# top_schem.net
KiCad netlist of a schematic drawn in Altium Designer
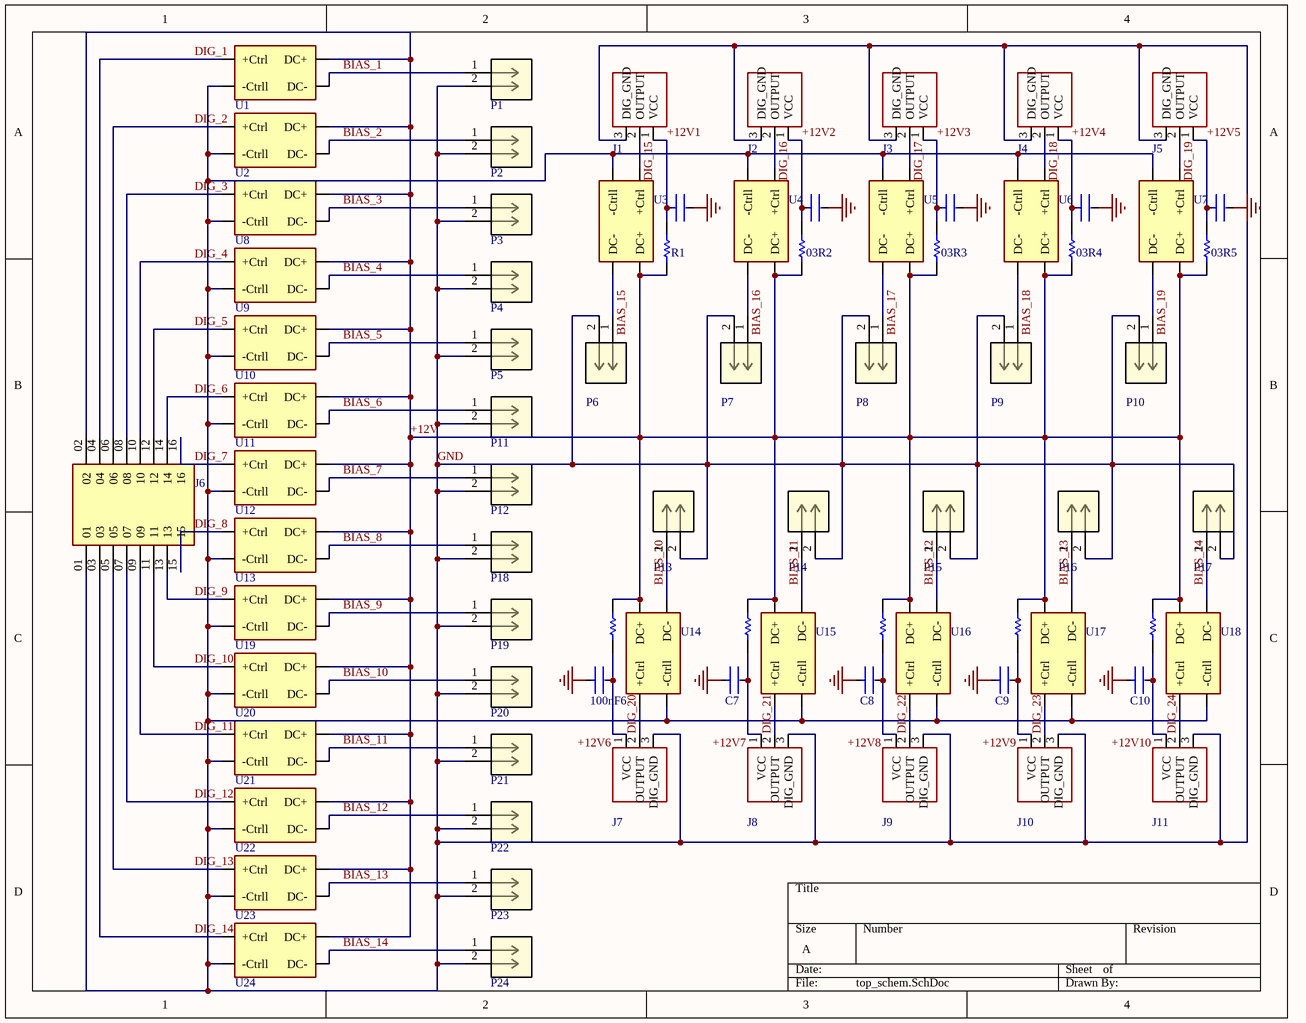
[diagram p0: top_schem.SchDoc]

(export (version "E")
  (design (tool "Eeschema 10.0.6"))
  (components
    (comp (ref "03R2")
      (value "ERJ-2BQJR30X")
      (footprint "03 Ohm")
      (description "RES 0.3 OHM 5% 1/6W 0402")
      (fields (field (name "MANUFACTURER") "Panasonic") (field (name "TOLERANCE") "5%"))
      (libsource (lib "ps_schlib") (part "ERJ-2BQJR30X"))
    )
    (comp (ref "03R3")
      (value "ERJ-2BQJR30X")
      (footprint "03 Ohm")
      (description "RES 0.3 OHM 5% 1/6W 0402")
      (fields (field (name "MANUFACTURER") "Panasonic") (field (name "TOLERANCE") "5%"))
      (libsource (lib "ps_schlib") (part "ERJ-2BQJR30X"))
    )
    (comp (ref "03R4")
      (value "ERJ-2BQJR30X")
      (footprint "03 Ohm")
      (description "RES 0.3 OHM 5% 1/6W 0402")
      (fields (field (name "MANUFACTURER") "Panasonic") (field (name "TOLERANCE") "5%"))
      (libsource (lib "ps_schlib") (part "ERJ-2BQJR30X"))
    )
    (comp (ref "03R5")
      (value "ERJ-2BQJR30X")
      (footprint "03 Ohm")
      (description "RES 0.3 OHM 5% 1/6W 0402")
      (fields (field (name "MANUFACTURER") "Panasonic") (field (name "TOLERANCE") "5%"))
      (libsource (lib "ps_schlib") (part "ERJ-2BQJR30X"))
    )
    (comp (ref "03R7")
      (value "ERJ-2BQJR30X")
      (footprint "03 Ohm")
      (description "RES 0.3 OHM 5% 1/6W 0402")
      (fields (field (name "MANUFACTURER") "Panasonic") (field (name "TOLERANCE") "5%"))
      (libsource (lib "ps_schlib") (part "ERJ-2BQJR30X"))
    )
    (comp (ref "03R8")
      (value "ERJ-2BQJR30X")
      (footprint "03 Ohm")
      (description "RES 0.3 OHM 5% 1/6W 0402")
      (fields (field (name "MANUFACTURER") "Panasonic") (field (name "TOLERANCE") "5%"))
      (libsource (lib "ps_schlib") (part "ERJ-2BQJR30X"))
    )
    (comp (ref "03R9")
      (value "ERJ-2BQJR30X")
      (footprint "03 Ohm")
      (description "RES 0.3 OHM 5% 1/6W 0402")
      (fields (field (name "MANUFACTURER") "Panasonic") (field (name "TOLERANCE") "5%"))
      (libsource (lib "ps_schlib") (part "ERJ-2BQJR30X"))
    )
    (comp (ref "03R10")
      (value "ERJ-2BQJR30X")
      (footprint "03 Ohm")
      (description "RES 0.3 OHM 5% 1/6W 0402")
      (fields (field (name "MANUFACTURER") "Panasonic") (field (name "TOLERANCE") "5%"))
      (libsource (lib "ps_schlib") (part "ERJ-2BQJR30X"))
    )
    (comp (ref "100nF1")
      (value "C0805C104K5RACTU")
      (footprint "100nF")
      (description "Cap Ceramic 0.1uF 50V X7R 10% SMD 2.0 x 1.2 mm 125 C Paper T/R")
      (fields (field (name "MANUFACTURER") "KEMET") (field (name "TOLERANCE") "10%"))
      (libsource (lib "ps_schlib") (part "C0805C104K5RACTU"))
    )
    (comp (ref "100nF6")
      (value "C0805C104K5RACTU")
      (footprint "100nF")
      (description "Cap Ceramic 0.1uF 50V X7R 10% SMD 2.0 x 1.2 mm 125 C Paper T/R")
      (fields (field (name "MANUFACTURER") "KEMET") (field (name "TOLERANCE") "10%"))
      (libsource (lib "ps_schlib") (part "C0805C104K5RACTU"))
    )
    (comp (ref "C2")
      (value "C0805C104K5RACTU")
      (footprint "100nF")
      (description "Cap Ceramic 0.1uF 50V X7R 10% SMD 2.0 x 1.2 mm 125 C Paper T/R")
      (fields (field (name "MANUFACTURER") "KEMET") (field (name "TOLERANCE") "10%"))
      (libsource (lib "ps_schlib") (part "C0805C104K5RACTU"))
    )
    (comp (ref "C3")
      (value "C0805C104K5RACTU")
      (footprint "100nF")
      (description "Cap Ceramic 0.1uF 50V X7R 10% SMD 2.0 x 1.2 mm 125 C Paper T/R")
      (fields (field (name "MANUFACTURER") "KEMET") (field (name "TOLERANCE") "10%"))
      (libsource (lib "ps_schlib") (part "C0805C104K5RACTU"))
    )
    (comp (ref "C4")
      (value "C0805C104K5RACTU")
      (footprint "100nF")
      (description "Cap Ceramic 0.1uF 50V X7R 10% SMD 2.0 x 1.2 mm 125 C Paper T/R")
      (fields (field (name "MANUFACTURER") "KEMET") (field (name "TOLERANCE") "10%"))
      (libsource (lib "ps_schlib") (part "C0805C104K5RACTU"))
    )
    (comp (ref "C5")
      (value "C0805C104K5RACTU")
      (footprint "100nF")
      (description "Cap Ceramic 0.1uF 50V X7R 10% SMD 2.0 x 1.2 mm 125 C Paper T/R")
      (fields (field (name "MANUFACTURER") "KEMET") (field (name "TOLERANCE") "10%"))
      (libsource (lib "ps_schlib") (part "C0805C104K5RACTU"))
    )
    (comp (ref "C7")
      (value "C0805C104K5RACTU")
      (footprint "100nF")
      (description "Cap Ceramic 0.1uF 50V X7R 10% SMD 2.0 x 1.2 mm 125 C Paper T/R")
      (fields (field (name "MANUFACTURER") "KEMET") (field (name "TOLERANCE") "10%"))
      (libsource (lib "ps_schlib") (part "C0805C104K5RACTU"))
    )
    (comp (ref "C8")
      (value "C0805C104K5RACTU")
      (footprint "100nF")
      (description "Cap Ceramic 0.1uF 50V X7R 10% SMD 2.0 x 1.2 mm 125 C Paper T/R")
      (fields (field (name "MANUFACTURER") "KEMET") (field (name "TOLERANCE") "10%"))
      (libsource (lib "ps_schlib") (part "C0805C104K5RACTU"))
    )
    (comp (ref "C9")
      (value "C0805C104K5RACTU")
      (footprint "100nF")
      (description "Cap Ceramic 0.1uF 50V X7R 10% SMD 2.0 x 1.2 mm 125 C Paper T/R")
      (fields (field (name "MANUFACTURER") "KEMET") (field (name "TOLERANCE") "10%"))
      (libsource (lib "ps_schlib") (part "C0805C104K5RACTU"))
    )
    (comp (ref "C10")
      (value "C0805C104K5RACTU")
      (footprint "100nF")
      (description "Cap Ceramic 0.1uF 50V X7R 10% SMD 2.0 x 1.2 mm 125 C Paper T/R")
      (fields (field (name "MANUFACTURER") "KEMET") (field (name "TOLERANCE") "10%"))
      (libsource (lib "ps_schlib") (part "C0805C104K5RACTU"))
    )
    (comp (ref "J1")
      (value "IF-D95T")
      (footprint "IF-D95")
      (description "DETECTOR PHOTOLOGIC TTL/CMOS")
      (fields (field (name "MANUFACTURER") "Industrial Fiber Optics"))
      (libsource (lib "ps_schlib") (part "IF-D95T"))
    )
    (comp (ref "J2")
      (value "IF-D95T")
      (footprint "IF-D95")
      (description "DETECTOR PHOTOLOGIC TTL/CMOS")
      (fields (field (name "MANUFACTURER") "Industrial Fiber Optics"))
      (libsource (lib "ps_schlib") (part "IF-D95T"))
    )
    (comp (ref "J3")
      (value "IF-D95T")
      (footprint "IF-D95")
      (description "DETECTOR PHOTOLOGIC TTL/CMOS")
      (fields (field (name "MANUFACTURER") "Industrial Fiber Optics"))
      (libsource (lib "ps_schlib") (part "IF-D95T"))
    )
    (comp (ref "J4")
      (value "IF-D95T")
      (footprint "IF-D95")
      (description "DETECTOR PHOTOLOGIC TTL/CMOS")
      (fields (field (name "MANUFACTURER") "Industrial Fiber Optics"))
      (libsource (lib "ps_schlib") (part "IF-D95T"))
    )
    (comp (ref "J5")
      (value "IF-D95T")
      (footprint "IF-D95")
      (description "DETECTOR PHOTOLOGIC TTL/CMOS")
      (fields (field (name "MANUFACTURER") "Industrial Fiber Optics"))
      (libsource (lib "ps_schlib") (part "IF-D95T"))
    )
    (comp (ref "J6")
      (value "SSM-108-X-DV")
      (footprint "16 pin header")
      (libsource (lib "ps_schlib") (part "SSM-108-X-DV"))
    )
    (comp (ref "J7")
      (value "IF-D95T")
      (footprint "IF-D95")
      (description "DETECTOR PHOTOLOGIC TTL/CMOS")
      (fields (field (name "MANUFACTURER") "Industrial Fiber Optics"))
      (libsource (lib "ps_schlib") (part "IF-D95T"))
    )
    (comp (ref "J8")
      (value "IF-D95T")
      (footprint "IF-D95")
      (description "DETECTOR PHOTOLOGIC TTL/CMOS")
      (fields (field (name "MANUFACTURER") "Industrial Fiber Optics"))
      (libsource (lib "ps_schlib") (part "IF-D95T"))
    )
    (comp (ref "J9")
      (value "IF-D95T")
      (footprint "IF-D95")
      (description "DETECTOR PHOTOLOGIC TTL/CMOS")
      (fields (field (name "MANUFACTURER") "Industrial Fiber Optics"))
      (libsource (lib "ps_schlib") (part "IF-D95T"))
    )
    (comp (ref "J10")
      (value "IF-D95T")
      (footprint "IF-D95")
      (description "DETECTOR PHOTOLOGIC TTL/CMOS")
      (fields (field (name "MANUFACTURER") "Industrial Fiber Optics"))
      (libsource (lib "ps_schlib") (part "IF-D95T"))
    )
    (comp (ref "J11")
      (value "IF-D95T")
      (footprint "IF-D95")
      (description "DETECTOR PHOTOLOGIC TTL/CMOS")
      (fields (field (name "MANUFACTURER") "Industrial Fiber Optics"))
      (libsource (lib "ps_schlib") (part "IF-D95T"))
    )
    (comp (ref "P1")
      (value "1054311102")
      (footprint "CONN_1054311102_MOL")
      (fields (field (name "MANUFACTURER") "Molex"))
      (libsource (lib "ps_schlib") (part "1054311102"))
    )
    (comp (ref "P2")
      (value "1054311102")
      (footprint "CONN_1054311102_MOL")
      (fields (field (name "MANUFACTURER") "Molex"))
      (libsource (lib "ps_schlib") (part "1054311102"))
    )
    (comp (ref "P3")
      (value "1054311102")
      (footprint "CONN_1054311102_MOL")
      (fields (field (name "MANUFACTURER") "Molex"))
      (libsource (lib "ps_schlib") (part "1054311102"))
    )
    (comp (ref "P4")
      (value "1054311102")
      (footprint "CONN_1054311102_MOL")
      (fields (field (name "MANUFACTURER") "Molex"))
      (libsource (lib "ps_schlib") (part "1054311102"))
    )
    (comp (ref "P5")
      (value "1054311102")
      (footprint "CONN_1054311102_MOL")
      (fields (field (name "MANUFACTURER") "Molex"))
      (libsource (lib "ps_schlib") (part "1054311102"))
    )
    (comp (ref "P6")
      (value "1054311102")
      (footprint "CONN_1054311102_MOL")
      (fields (field (name "MANUFACTURER") "Molex"))
      (libsource (lib "") (part "1054311102_1"))
    )
    (comp (ref "P7")
      (value "1054311102")
      (footprint "CONN_1054311102_MOL")
      (fields (field (name "MANUFACTURER") "Molex"))
      (libsource (lib "") (part "1054311102_1"))
    )
    (comp (ref "P8")
      (value "1054311102")
      (footprint "CONN_1054311102_MOL")
      (fields (field (name "MANUFACTURER") "Molex"))
      (libsource (lib "") (part "1054311102_1"))
    )
    (comp (ref "P9")
      (value "1054311102")
      (footprint "CONN_1054311102_MOL")
      (fields (field (name "MANUFACTURER") "Molex"))
      (libsource (lib "") (part "1054311102_1"))
    )
    (comp (ref "P10")
      (value "1054311102")
      (footprint "CONN_1054311102_MOL")
      (fields (field (name "MANUFACTURER") "Molex"))
      (libsource (lib "") (part "1054311102_1"))
    )
    (comp (ref "P11")
      (value "1054311102")
      (footprint "CONN_1054311102_MOL")
      (fields (field (name "MANUFACTURER") "Molex"))
      (libsource (lib "ps_schlib") (part "1054311102"))
    )
    (comp (ref "P12")
      (value "1054311102")
      (footprint "CONN_1054311102_MOL")
      (fields (field (name "MANUFACTURER") "Molex"))
      (libsource (lib "ps_schlib") (part "1054311102"))
    )
    (comp (ref "P13")
      (value "1054311102")
      (footprint "CONN_1054311102_MOL")
      (fields (field (name "MANUFACTURER") "Molex"))
      (libsource (lib "") (part "1054311102_2"))
    )
    (comp (ref "P14")
      (value "1054311102")
      (footprint "CONN_1054311102_MOL")
      (fields (field (name "MANUFACTURER") "Molex"))
      (libsource (lib "") (part "1054311102_2"))
    )
    (comp (ref "P15")
      (value "1054311102")
      (footprint "CONN_1054311102_MOL")
      (fields (field (name "MANUFACTURER") "Molex"))
      (libsource (lib "") (part "1054311102_2"))
    )
    (comp (ref "P16")
      (value "1054311102")
      (footprint "CONN_1054311102_MOL")
      (fields (field (name "MANUFACTURER") "Molex"))
      (libsource (lib "") (part "1054311102_2"))
    )
    (comp (ref "P17")
      (value "1054311102")
      (footprint "CONN_1054311102_MOL")
      (fields (field (name "MANUFACTURER") "Molex"))
      (libsource (lib "") (part "1054311102_2"))
    )
    (comp (ref "P18")
      (value "1054311102")
      (footprint "CONN_1054311102_MOL")
      (fields (field (name "MANUFACTURER") "Molex"))
      (libsource (lib "ps_schlib") (part "1054311102"))
    )
    (comp (ref "P19")
      (value "1054311102")
      (footprint "CONN_1054311102_MOL")
      (fields (field (name "MANUFACTURER") "Molex"))
      (libsource (lib "ps_schlib") (part "1054311102"))
    )
    (comp (ref "P20")
      (value "1054311102")
      (footprint "CONN_1054311102_MOL")
      (fields (field (name "MANUFACTURER") "Molex"))
      (libsource (lib "ps_schlib") (part "1054311102"))
    )
    (comp (ref "P21")
      (value "1054311102")
      (footprint "CONN_1054311102_MOL")
      (fields (field (name "MANUFACTURER") "Molex"))
      (libsource (lib "ps_schlib") (part "1054311102"))
    )
    (comp (ref "P22")
      (value "1054311102")
      (footprint "CONN_1054311102_MOL")
      (fields (field (name "MANUFACTURER") "Molex"))
      (libsource (lib "ps_schlib") (part "1054311102"))
    )
    (comp (ref "P23")
      (value "1054311102")
      (footprint "CONN_1054311102_MOL")
      (fields (field (name "MANUFACTURER") "Molex"))
      (libsource (lib "ps_schlib") (part "1054311102"))
    )
    (comp (ref "P24")
      (value "1054311102")
      (footprint "CONN_1054311102_MOL")
      (fields (field (name "MANUFACTURER") "Molex"))
      (libsource (lib "ps_schlib") (part "1054311102"))
    )
    (comp (ref "R1")
      (value "ERJ-2BQJR30X")
      (footprint "03 Ohm")
      (description "RES 0.3 OHM 5% 1/6W 0402")
      (fields (field (name "MANUFACTURER") "Panasonic") (field (name "TOLERANCE") "5%"))
      (libsource (lib "ps_schlib") (part "ERJ-2BQJR30X"))
    )
    (comp (ref "R6")
      (value "ERJ-2BQJR30X")
      (footprint "03 Ohm")
      (description "RES 0.3 OHM 5% 1/6W 0402")
      (fields (field (name "MANUFACTURER") "Panasonic") (field (name "TOLERANCE") "5%"))
      (libsource (lib "ps_schlib") (part "ERJ-2BQJR30X"))
    )
    (comp (ref "U1")
      (value "Solid state relay")
      (footprint "CPC1002N")
      (libsource (lib "ps_schlib") (part "CPC1002N"))
    )
    (comp (ref "U2")
      (value "Solid state relay")
      (footprint "CPC1002N")
      (libsource (lib "ps_schlib") (part "CPC1002N"))
    )
    (comp (ref "U3")
      (value "Solid state relay")
      (footprint "CPC1002N")
      (libsource (lib "") (part "CPC1002N_2"))
    )
    (comp (ref "U4")
      (value "Solid state relay")
      (footprint "CPC1002N")
      (libsource (lib "") (part "CPC1002N_2"))
    )
    (comp (ref "U5")
      (value "Solid state relay")
      (footprint "CPC1002N")
      (libsource (lib "") (part "CPC1002N_2"))
    )
    (comp (ref "U6")
      (value "Solid state relay")
      (footprint "CPC1002N")
      (libsource (lib "") (part "CPC1002N_2"))
    )
    (comp (ref "U7")
      (value "Solid state relay")
      (footprint "CPC1002N")
      (libsource (lib "") (part "CPC1002N_2"))
    )
    (comp (ref "U8")
      (value "Solid state relay")
      (footprint "CPC1002N")
      (libsource (lib "ps_schlib") (part "CPC1002N"))
    )
    (comp (ref "U9")
      (value "Solid state relay")
      (footprint "CPC1002N")
      (libsource (lib "ps_schlib") (part "CPC1002N"))
    )
    (comp (ref "U10")
      (value "Solid state relay")
      (footprint "CPC1002N")
      (libsource (lib "ps_schlib") (part "CPC1002N"))
    )
    (comp (ref "U11")
      (value "Solid state relay")
      (footprint "CPC1002N")
      (libsource (lib "ps_schlib") (part "CPC1002N"))
    )
    (comp (ref "U12")
      (value "Solid state relay")
      (footprint "CPC1002N")
      (libsource (lib "ps_schlib") (part "CPC1002N"))
    )
    (comp (ref "U13")
      (value "Solid state relay")
      (footprint "CPC1002N")
      (libsource (lib "ps_schlib") (part "CPC1002N"))
    )
    (comp (ref "U14")
      (value "Solid state relay")
      (footprint "CPC1002N")
      (libsource (lib "") (part "CPC1002N_1"))
    )
    (comp (ref "U15")
      (value "Solid state relay")
      (footprint "CPC1002N")
      (libsource (lib "") (part "CPC1002N_1"))
    )
    (comp (ref "U16")
      (value "Solid state relay")
      (footprint "CPC1002N")
      (libsource (lib "") (part "CPC1002N_1"))
    )
    (comp (ref "U17")
      (value "Solid state relay")
      (footprint "CPC1002N")
      (libsource (lib "") (part "CPC1002N_1"))
    )
    (comp (ref "U18")
      (value "Solid state relay")
      (footprint "CPC1002N")
      (libsource (lib "") (part "CPC1002N_1"))
    )
    (comp (ref "U19")
      (value "Solid state relay")
      (footprint "CPC1002N")
      (libsource (lib "ps_schlib") (part "CPC1002N"))
    )
    (comp (ref "U20")
      (value "Solid state relay")
      (footprint "CPC1002N")
      (libsource (lib "ps_schlib") (part "CPC1002N"))
    )
    (comp (ref "U21")
      (value "Solid state relay")
      (footprint "CPC1002N")
      (libsource (lib "ps_schlib") (part "CPC1002N"))
    )
    (comp (ref "U22")
      (value "Solid state relay")
      (footprint "CPC1002N")
      (libsource (lib "ps_schlib") (part "CPC1002N"))
    )
    (comp (ref "U23")
      (value "Solid state relay")
      (footprint "CPC1002N")
      (libsource (lib "ps_schlib") (part "CPC1002N"))
    )
    (comp (ref "U24")
      (value "Solid state relay")
      (footprint "CPC1002N")
      (libsource (lib "ps_schlib") (part "CPC1002N"))
    )
  )
  (nets
    (net (code "1") (name "/+12V") (class "Default")
      (node (ref "03R10") (pin "2") (pinfunction "2_2") (pintype "passive"))
      (node (ref "03R2") (pin "1") (pinfunction "1_1") (pintype "passive"))
      (node (ref "03R3") (pin "1") (pinfunction "1_1") (pintype "passive"))
      (node (ref "03R4") (pin "1") (pinfunction "1_1") (pintype "passive"))
      (node (ref "03R5") (pin "1") (pinfunction "1_1") (pintype "passive"))
      (node (ref "03R7") (pin "2") (pinfunction "2_2") (pintype "passive"))
      (node (ref "03R8") (pin "2") (pinfunction "2_2") (pintype "passive"))
      (node (ref "03R9") (pin "2") (pinfunction "2_2") (pintype "passive"))
      (node (ref "J6") (pin "02") (pinfunction "02_02") (pintype "passive"))
      (node (ref "R1") (pin "1") (pinfunction "1_1") (pintype "passive"))
      (node (ref "R6") (pin "2") (pinfunction "2_2") (pintype "passive"))
      (node (ref "U1") (pin "4") (pinfunction "DC+_4") (pintype "passive"))
      (node (ref "U10") (pin "4") (pinfunction "DC+_4") (pintype "passive"))
      (node (ref "U11") (pin "4") (pinfunction "DC+_4") (pintype "passive"))
      (node (ref "U12") (pin "4") (pinfunction "DC+_4") (pintype "passive"))
      (node (ref "U13") (pin "4") (pinfunction "DC+_4") (pintype "passive"))
      (node (ref "U14") (pin "4") (pinfunction "DC+_4") (pintype "passive"))
      (node (ref "U15") (pin "4") (pinfunction "DC+_4") (pintype "passive"))
      (node (ref "U16") (pin "4") (pinfunction "DC+_4") (pintype "passive"))
      (node (ref "U17") (pin "4") (pinfunction "DC+_4") (pintype "passive"))
      (node (ref "U18") (pin "4") (pinfunction "DC+_4") (pintype "passive"))
      (node (ref "U19") (pin "4") (pinfunction "DC+_4") (pintype "passive"))
      (node (ref "U2") (pin "4") (pinfunction "DC+_4") (pintype "passive"))
      (node (ref "U20") (pin "4") (pinfunction "DC+_4") (pintype "passive"))
      (node (ref "U21") (pin "4") (pinfunction "DC+_4") (pintype "passive"))
      (node (ref "U22") (pin "4") (pinfunction "DC+_4") (pintype "passive"))
      (node (ref "U23") (pin "4") (pinfunction "DC+_4") (pintype "passive"))
      (node (ref "U24") (pin "4") (pinfunction "DC+_4") (pintype "passive"))
      (node (ref "U3") (pin "4") (pinfunction "DC+_4") (pintype "passive"))
      (node (ref "U4") (pin "4") (pinfunction "DC+_4") (pintype "passive"))
      (node (ref "U5") (pin "4") (pinfunction "DC+_4") (pintype "passive"))
      (node (ref "U6") (pin "4") (pinfunction "DC+_4") (pintype "passive"))
      (node (ref "U7") (pin "4") (pinfunction "DC+_4") (pintype "passive"))
      (node (ref "U8") (pin "4") (pinfunction "DC+_4") (pintype "passive"))
      (node (ref "U9") (pin "4") (pinfunction "DC+_4") (pintype "passive"))
    )
    (net (code "2") (name "/+12V1") (class "Default")
      (node (ref "100nF1") (pin "1") (pinfunction "1_1") (pintype "passive"))
      (node (ref "J1") (pin "1") (pinfunction "VCC_1") (pintype "passive"))
      (node (ref "R1") (pin "2") (pinfunction "2_2") (pintype "passive"))
    )
    (net (code "3") (name "/+12V2") (class "Default")
      (node (ref "03R2") (pin "2") (pinfunction "2_2") (pintype "passive"))
      (node (ref "C2") (pin "1") (pinfunction "1_1") (pintype "passive"))
      (node (ref "J2") (pin "1") (pinfunction "VCC_1") (pintype "passive"))
    )
    (net (code "4") (name "/+12V3") (class "Default")
      (node (ref "03R3") (pin "2") (pinfunction "2_2") (pintype "passive"))
      (node (ref "C3") (pin "1") (pinfunction "1_1") (pintype "passive"))
      (node (ref "J3") (pin "1") (pinfunction "VCC_1") (pintype "passive"))
    )
    (net (code "5") (name "/+12V4") (class "Default")
      (node (ref "03R4") (pin "2") (pinfunction "2_2") (pintype "passive"))
      (node (ref "C4") (pin "1") (pinfunction "1_1") (pintype "passive"))
      (node (ref "J4") (pin "1") (pinfunction "VCC_1") (pintype "passive"))
    )
    (net (code "6") (name "/+12V5") (class "Default")
      (node (ref "03R5") (pin "2") (pinfunction "2_2") (pintype "passive"))
      (node (ref "C5") (pin "1") (pinfunction "1_1") (pintype "passive"))
      (node (ref "J5") (pin "1") (pinfunction "VCC_1") (pintype "passive"))
    )
    (net (code "7") (name "/+12V6") (class "Default")
      (node (ref "100nF6") (pin "2") (pinfunction "2_2") (pintype "passive"))
      (node (ref "J7") (pin "1") (pinfunction "VCC_1") (pintype "passive"))
      (node (ref "R6") (pin "1") (pinfunction "1_1") (pintype "passive"))
    )
    (net (code "8") (name "/+12V7") (class "Default")
      (node (ref "03R7") (pin "1") (pinfunction "1_1") (pintype "passive"))
      (node (ref "C7") (pin "2") (pinfunction "2_2") (pintype "passive"))
      (node (ref "J8") (pin "1") (pinfunction "VCC_1") (pintype "passive"))
    )
    (net (code "9") (name "/+12V8") (class "Default")
      (node (ref "03R8") (pin "1") (pinfunction "1_1") (pintype "passive"))
      (node (ref "C8") (pin "2") (pinfunction "2_2") (pintype "passive"))
      (node (ref "J9") (pin "1") (pinfunction "VCC_1") (pintype "passive"))
    )
    (net (code "10") (name "/+12V9") (class "Default")
      (node (ref "03R9") (pin "1") (pinfunction "1_1") (pintype "passive"))
      (node (ref "C9") (pin "2") (pinfunction "2_2") (pintype "passive"))
      (node (ref "J10") (pin "1") (pinfunction "VCC_1") (pintype "passive"))
    )
    (net (code "11") (name "/+12V10") (class "Default")
      (node (ref "03R10") (pin "1") (pinfunction "1_1") (pintype "passive"))
      (node (ref "C10") (pin "2") (pinfunction "2_2") (pintype "passive"))
      (node (ref "J11") (pin "1") (pinfunction "VCC_1") (pintype "passive"))
    )
    (net (code "12") (name "/BIAS_1") (class "Default")
      (node (ref "P1") (pin "1") (pinfunction "1_1") (pintype "passive"))
      (node (ref "U1") (pin "3") (pinfunction "DC-_3") (pintype "passive"))
    )
    (net (code "13") (name "/BIAS_2") (class "Default")
      (node (ref "P2") (pin "1") (pinfunction "1_1") (pintype "passive"))
      (node (ref "U2") (pin "3") (pinfunction "DC-_3") (pintype "passive"))
    )
    (net (code "14") (name "/BIAS_3") (class "Default")
      (node (ref "P3") (pin "1") (pinfunction "1_1") (pintype "passive"))
      (node (ref "U8") (pin "3") (pinfunction "DC-_3") (pintype "passive"))
    )
    (net (code "15") (name "/BIAS_4") (class "Default")
      (node (ref "P4") (pin "1") (pinfunction "1_1") (pintype "passive"))
      (node (ref "U9") (pin "3") (pinfunction "DC-_3") (pintype "passive"))
    )
    (net (code "16") (name "/BIAS_5") (class "Default")
      (node (ref "P5") (pin "1") (pinfunction "1_1") (pintype "passive"))
      (node (ref "U10") (pin "3") (pinfunction "DC-_3") (pintype "passive"))
    )
    (net (code "17") (name "/BIAS_6") (class "Default")
      (node (ref "P11") (pin "1") (pinfunction "1_1") (pintype "passive"))
      (node (ref "U11") (pin "3") (pinfunction "DC-_3") (pintype "passive"))
    )
    (net (code "18") (name "/BIAS_7") (class "Default")
      (node (ref "P12") (pin "1") (pinfunction "1_1") (pintype "passive"))
      (node (ref "U12") (pin "3") (pinfunction "DC-_3") (pintype "passive"))
    )
    (net (code "19") (name "/BIAS_8") (class "Default")
      (node (ref "P18") (pin "1") (pinfunction "1_1") (pintype "passive"))
      (node (ref "U13") (pin "3") (pinfunction "DC-_3") (pintype "passive"))
    )
    (net (code "20") (name "/BIAS_9") (class "Default")
      (node (ref "P19") (pin "1") (pinfunction "1_1") (pintype "passive"))
      (node (ref "U19") (pin "3") (pinfunction "DC-_3") (pintype "passive"))
    )
    (net (code "21") (name "/BIAS_10") (class "Default")
      (node (ref "P20") (pin "1") (pinfunction "1_1") (pintype "passive"))
      (node (ref "U20") (pin "3") (pinfunction "DC-_3") (pintype "passive"))
    )
    (net (code "22") (name "/BIAS_11") (class "Default")
      (node (ref "P21") (pin "1") (pinfunction "1_1") (pintype "passive"))
      (node (ref "U21") (pin "3") (pinfunction "DC-_3") (pintype "passive"))
    )
    (net (code "23") (name "/BIAS_12") (class "Default")
      (node (ref "P22") (pin "1") (pinfunction "1_1") (pintype "passive"))
      (node (ref "U22") (pin "3") (pinfunction "DC-_3") (pintype "passive"))
    )
    (net (code "24") (name "/BIAS_13") (class "Default")
      (node (ref "P23") (pin "1") (pinfunction "1_1") (pintype "passive"))
      (node (ref "U23") (pin "3") (pinfunction "DC-_3") (pintype "passive"))
    )
    (net (code "25") (name "/BIAS_14") (class "Default")
      (node (ref "P24") (pin "1") (pinfunction "1_1") (pintype "passive"))
      (node (ref "U24") (pin "3") (pinfunction "DC-_3") (pintype "passive"))
    )
    (net (code "26") (name "/BIAS_15") (class "Default")
      (node (ref "P6") (pin "1") (pinfunction "1_1") (pintype "passive"))
      (node (ref "U3") (pin "3") (pinfunction "DC-_3") (pintype "passive"))
    )
    (net (code "27") (name "/BIAS_16") (class "Default")
      (node (ref "P7") (pin "1") (pinfunction "1_1") (pintype "passive"))
      (node (ref "U4") (pin "3") (pinfunction "DC-_3") (pintype "passive"))
    )
    (net (code "28") (name "/BIAS_17") (class "Default")
      (node (ref "P8") (pin "1") (pinfunction "1_1") (pintype "passive"))
      (node (ref "U5") (pin "3") (pinfunction "DC-_3") (pintype "passive"))
    )
    (net (code "29") (name "/BIAS_18") (class "Default")
      (node (ref "P9") (pin "1") (pinfunction "1_1") (pintype "passive"))
      (node (ref "U6") (pin "3") (pinfunction "DC-_3") (pintype "passive"))
    )
    (net (code "30") (name "/BIAS_19") (class "Default")
      (node (ref "P10") (pin "1") (pinfunction "1_1") (pintype "passive"))
      (node (ref "U7") (pin "3") (pinfunction "DC-_3") (pintype "passive"))
    )
    (net (code "31") (name "/BIAS_20") (class "Default")
      (node (ref "P13") (pin "1") (pinfunction "1_1") (pintype "passive"))
      (node (ref "U14") (pin "3") (pinfunction "DC-_3") (pintype "passive"))
    )
    (net (code "32") (name "/BIAS_21") (class "Default")
      (node (ref "P14") (pin "1") (pinfunction "1_1") (pintype "passive"))
      (node (ref "U15") (pin "3") (pinfunction "DC-_3") (pintype "passive"))
    )
    (net (code "33") (name "/BIAS_22") (class "Default")
      (node (ref "P15") (pin "1") (pinfunction "1_1") (pintype "passive"))
      (node (ref "U16") (pin "3") (pinfunction "DC-_3") (pintype "passive"))
    )
    (net (code "34") (name "/BIAS_23") (class "Default")
      (node (ref "P16") (pin "1") (pinfunction "1_1") (pintype "passive"))
      (node (ref "U17") (pin "3") (pinfunction "DC-_3") (pintype "passive"))
    )
    (net (code "35") (name "/BIAS_24") (class "Default")
      (node (ref "P17") (pin "1") (pinfunction "1_1") (pintype "passive"))
      (node (ref "U18") (pin "3") (pinfunction "DC-_3") (pintype "passive"))
    )
    (net (code "36") (name "/DIG_1") (class "Default")
      (node (ref "J6") (pin "04") (pinfunction "04_04") (pintype "passive"))
      (node (ref "U1") (pin "1") (pinfunction "+Ctrl_1") (pintype "passive"))
    )
    (net (code "37") (name "/DIG_2") (class "Default")
      (node (ref "J6") (pin "06") (pinfunction "06_06") (pintype "passive"))
      (node (ref "U2") (pin "1") (pinfunction "+Ctrl_1") (pintype "passive"))
    )
    (net (code "38") (name "/DIG_3") (class "Default")
      (node (ref "J6") (pin "08") (pinfunction "08_08") (pintype "passive"))
      (node (ref "U8") (pin "1") (pinfunction "+Ctrl_1") (pintype "passive"))
    )
    (net (code "39") (name "/DIG_4") (class "Default")
      (node (ref "J6") (pin "10") (pinfunction "10_10") (pintype "passive"))
      (node (ref "U9") (pin "1") (pinfunction "+Ctrl_1") (pintype "passive"))
    )
    (net (code "40") (name "/DIG_5") (class "Default")
      (node (ref "J6") (pin "12") (pinfunction "12_12") (pintype "passive"))
      (node (ref "U10") (pin "1") (pinfunction "+Ctrl_1") (pintype "passive"))
    )
    (net (code "41") (name "/DIG_6") (class "Default")
      (node (ref "J6") (pin "14") (pinfunction "14_14") (pintype "passive"))
      (node (ref "U11") (pin "1") (pinfunction "+Ctrl_1") (pintype "passive"))
    )
    (net (code "42") (name "/DIG_7") (class "Default")
      (node (ref "J6") (pin "16") (pinfunction "16_16") (pintype "passive"))
      (node (ref "U12") (pin "1") (pinfunction "+Ctrl_1") (pintype "passive"))
    )
    (net (code "43") (name "/DIG_8") (class "Default")
      (node (ref "J6") (pin "15") (pinfunction "15_15") (pintype "passive"))
      (node (ref "U13") (pin "1") (pinfunction "+Ctrl_1") (pintype "passive"))
    )
    (net (code "44") (name "/DIG_9") (class "Default")
      (node (ref "J6") (pin "13") (pinfunction "13_13") (pintype "passive"))
      (node (ref "U19") (pin "1") (pinfunction "+Ctrl_1") (pintype "passive"))
    )
    (net (code "45") (name "/DIG_10") (class "Default")
      (node (ref "J6") (pin "11") (pinfunction "11_11") (pintype "passive"))
      (node (ref "U20") (pin "1") (pinfunction "+Ctrl_1") (pintype "passive"))
    )
    (net (code "46") (name "/DIG_11") (class "Default")
      (node (ref "J6") (pin "09") (pinfunction "09_09") (pintype "passive"))
      (node (ref "U21") (pin "1") (pinfunction "+Ctrl_1") (pintype "passive"))
    )
    (net (code "47") (name "/DIG_12") (class "Default")
      (node (ref "J6") (pin "07") (pinfunction "07_07") (pintype "passive"))
      (node (ref "U22") (pin "1") (pinfunction "+Ctrl_1") (pintype "passive"))
    )
    (net (code "48") (name "/DIG_13") (class "Default")
      (node (ref "J6") (pin "05") (pinfunction "05_05") (pintype "passive"))
      (node (ref "U23") (pin "1") (pinfunction "+Ctrl_1") (pintype "passive"))
    )
    (net (code "49") (name "/DIG_14") (class "Default")
      (node (ref "J6") (pin "03") (pinfunction "03_03") (pintype "passive"))
      (node (ref "U24") (pin "1") (pinfunction "+Ctrl_1") (pintype "passive"))
    )
    (net (code "50") (name "/DIG_15") (class "Default")
      (node (ref "J1") (pin "2") (pinfunction "OUTPUT_2") (pintype "passive"))
      (node (ref "U3") (pin "1") (pinfunction "+Ctrl_1") (pintype "passive"))
    )
    (net (code "51") (name "/DIG_16") (class "Default")
      (node (ref "J2") (pin "2") (pinfunction "OUTPUT_2") (pintype "passive"))
      (node (ref "U4") (pin "1") (pinfunction "+Ctrl_1") (pintype "passive"))
    )
    (net (code "52") (name "/DIG_17") (class "Default")
      (node (ref "J3") (pin "2") (pinfunction "OUTPUT_2") (pintype "passive"))
      (node (ref "U5") (pin "1") (pinfunction "+Ctrl_1") (pintype "passive"))
    )
    (net (code "53") (name "/DIG_18") (class "Default")
      (node (ref "J4") (pin "2") (pinfunction "OUTPUT_2") (pintype "passive"))
      (node (ref "U6") (pin "1") (pinfunction "+Ctrl_1") (pintype "passive"))
    )
    (net (code "54") (name "/DIG_19") (class "Default")
      (node (ref "J5") (pin "2") (pinfunction "OUTPUT_2") (pintype "passive"))
      (node (ref "U7") (pin "1") (pinfunction "+Ctrl_1") (pintype "passive"))
    )
    (net (code "55") (name "/DIG_20") (class "Default")
      (node (ref "J7") (pin "2") (pinfunction "OUTPUT_2") (pintype "passive"))
      (node (ref "U14") (pin "1") (pinfunction "+Ctrl_1") (pintype "passive"))
    )
    (net (code "56") (name "/DIG_21") (class "Default")
      (node (ref "J8") (pin "2") (pinfunction "OUTPUT_2") (pintype "passive"))
      (node (ref "U15") (pin "1") (pinfunction "+Ctrl_1") (pintype "passive"))
    )
    (net (code "57") (name "/DIG_22") (class "Default")
      (node (ref "J9") (pin "2") (pinfunction "OUTPUT_2") (pintype "passive"))
      (node (ref "U16") (pin "1") (pinfunction "+Ctrl_1") (pintype "passive"))
    )
    (net (code "58") (name "/DIG_23") (class "Default")
      (node (ref "J10") (pin "2") (pinfunction "OUTPUT_2") (pintype "passive"))
      (node (ref "U17") (pin "1") (pinfunction "+Ctrl_1") (pintype "passive"))
    )
    (net (code "59") (name "/DIG_24") (class "Default")
      (node (ref "J11") (pin "2") (pinfunction "OUTPUT_2") (pintype "passive"))
      (node (ref "U18") (pin "1") (pinfunction "+Ctrl_1") (pintype "passive"))
    )
    (net (code "60") (name "GND") (class "Default")
      (node (ref "100nF1") (pin "2") (pinfunction "2_2") (pintype "passive"))
      (node (ref "100nF6") (pin "1") (pinfunction "1_1") (pintype "passive"))
      (node (ref "C10") (pin "1") (pinfunction "1_1") (pintype "passive"))
      (node (ref "C2") (pin "2") (pinfunction "2_2") (pintype "passive"))
      (node (ref "C3") (pin "2") (pinfunction "2_2") (pintype "passive"))
      (node (ref "C4") (pin "2") (pinfunction "2_2") (pintype "passive"))
      (node (ref "C5") (pin "2") (pinfunction "2_2") (pintype "passive"))
      (node (ref "C7") (pin "1") (pinfunction "1_1") (pintype "passive"))
      (node (ref "C8") (pin "1") (pinfunction "1_1") (pintype "passive"))
      (node (ref "C9") (pin "1") (pinfunction "1_1") (pintype "passive"))
      (node (ref "J1") (pin "3") (pinfunction "DIG_GND_3") (pintype "passive"))
      (node (ref "J10") (pin "3") (pinfunction "DIG_GND_3") (pintype "passive"))
      (node (ref "J11") (pin "3") (pinfunction "DIG_GND_3") (pintype "passive"))
      (node (ref "J2") (pin "3") (pinfunction "DIG_GND_3") (pintype "passive"))
      (node (ref "J3") (pin "3") (pinfunction "DIG_GND_3") (pintype "passive"))
      (node (ref "J4") (pin "3") (pinfunction "DIG_GND_3") (pintype "passive"))
      (node (ref "J5") (pin "3") (pinfunction "DIG_GND_3") (pintype "passive"))
      (node (ref "J6") (pin "01") (pinfunction "01_01") (pintype "passive"))
      (node (ref "J7") (pin "3") (pinfunction "DIG_GND_3") (pintype "passive"))
      (node (ref "J8") (pin "3") (pinfunction "DIG_GND_3") (pintype "passive"))
      (node (ref "J9") (pin "3") (pinfunction "DIG_GND_3") (pintype "passive"))
      (node (ref "P1") (pin "2") (pinfunction "2_2") (pintype "passive"))
      (node (ref "P10") (pin "2") (pinfunction "2_2") (pintype "passive"))
      (node (ref "P11") (pin "2") (pinfunction "2_2") (pintype "passive"))
      (node (ref "P12") (pin "2") (pinfunction "2_2") (pintype "passive"))
      (node (ref "P13") (pin "2") (pinfunction "2_2") (pintype "passive"))
      (node (ref "P14") (pin "2") (pinfunction "2_2") (pintype "passive"))
      (node (ref "P15") (pin "2") (pinfunction "2_2") (pintype "passive"))
      (node (ref "P16") (pin "2") (pinfunction "2_2") (pintype "passive"))
      (node (ref "P17") (pin "2") (pinfunction "2_2") (pintype "passive"))
      (node (ref "P18") (pin "2") (pinfunction "2_2") (pintype "passive"))
      (node (ref "P19") (pin "2") (pinfunction "2_2") (pintype "passive"))
      (node (ref "P2") (pin "2") (pinfunction "2_2") (pintype "passive"))
      (node (ref "P20") (pin "2") (pinfunction "2_2") (pintype "passive"))
      (node (ref "P21") (pin "2") (pinfunction "2_2") (pintype "passive"))
      (node (ref "P22") (pin "2") (pinfunction "2_2") (pintype "passive"))
      (node (ref "P23") (pin "2") (pinfunction "2_2") (pintype "passive"))
      (node (ref "P24") (pin "2") (pinfunction "2_2") (pintype "passive"))
      (node (ref "P3") (pin "2") (pinfunction "2_2") (pintype "passive"))
      (node (ref "P4") (pin "2") (pinfunction "2_2") (pintype "passive"))
      (node (ref "P5") (pin "2") (pinfunction "2_2") (pintype "passive"))
      (node (ref "P6") (pin "2") (pinfunction "2_2") (pintype "passive"))
      (node (ref "P7") (pin "2") (pinfunction "2_2") (pintype "passive"))
      (node (ref "P8") (pin "2") (pinfunction "2_2") (pintype "passive"))
      (node (ref "P9") (pin "2") (pinfunction "2_2") (pintype "passive"))
      (node (ref "U1") (pin "2") (pinfunction "-Ctrll_2") (pintype "passive"))
      (node (ref "U10") (pin "2") (pinfunction "-Ctrll_2") (pintype "passive"))
      (node (ref "U11") (pin "2") (pinfunction "-Ctrll_2") (pintype "passive"))
      (node (ref "U12") (pin "2") (pinfunction "-Ctrll_2") (pintype "passive"))
      (node (ref "U13") (pin "2") (pinfunction "-Ctrll_2") (pintype "passive"))
      (node (ref "U14") (pin "2") (pinfunction "-Ctrll_2") (pintype "passive"))
      (node (ref "U15") (pin "2") (pinfunction "-Ctrll_2") (pintype "passive"))
      (node (ref "U16") (pin "2") (pinfunction "-Ctrll_2") (pintype "passive"))
      (node (ref "U17") (pin "2") (pinfunction "-Ctrll_2") (pintype "passive"))
      (node (ref "U18") (pin "2") (pinfunction "-Ctrll_2") (pintype "passive"))
      (node (ref "U19") (pin "2") (pinfunction "-Ctrll_2") (pintype "passive"))
      (node (ref "U2") (pin "2") (pinfunction "-Ctrll_2") (pintype "passive"))
      (node (ref "U20") (pin "2") (pinfunction "-Ctrll_2") (pintype "passive"))
      (node (ref "U21") (pin "2") (pinfunction "-Ctrll_2") (pintype "passive"))
      (node (ref "U22") (pin "2") (pinfunction "-Ctrll_2") (pintype "passive"))
      (node (ref "U23") (pin "2") (pinfunction "-Ctrll_2") (pintype "passive"))
      (node (ref "U24") (pin "2") (pinfunction "-Ctrll_2") (pintype "passive"))
      (node (ref "U3") (pin "2") (pinfunction "-Ctrll_2") (pintype "passive"))
      (node (ref "U4") (pin "2") (pinfunction "-Ctrll_2") (pintype "passive"))
      (node (ref "U5") (pin "2") (pinfunction "-Ctrll_2") (pintype "passive"))
      (node (ref "U6") (pin "2") (pinfunction "-Ctrll_2") (pintype "passive"))
      (node (ref "U7") (pin "2") (pinfunction "-Ctrll_2") (pintype "passive"))
      (node (ref "U8") (pin "2") (pinfunction "-Ctrll_2") (pintype "passive"))
      (node (ref "U9") (pin "2") (pinfunction "-Ctrll_2") (pintype "passive"))
    )
  )
)
